# untitled.net
KiCad netlist of a schematic drawn in EAGLE
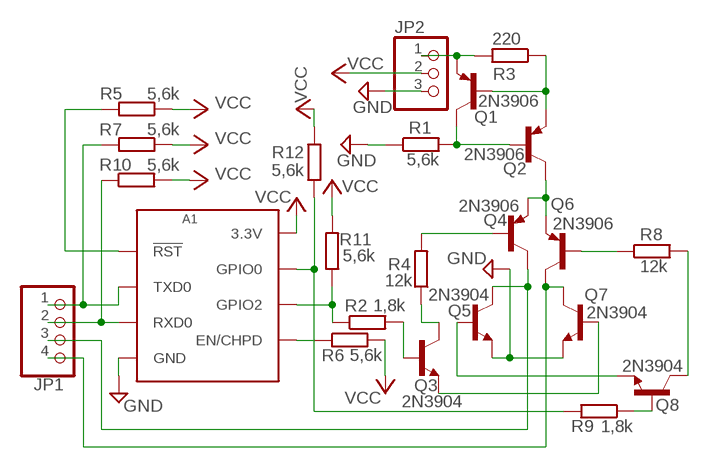
[diagram p0: schematic, sheet 1]

(export (version "E")
  (design (tool "Eeschema 10.0.6"))
  (components
    (comp (ref "A1")
      (value "ESP8266_ESP-01")
      (footprint "eagle-import:ESP8266_ESP-01_NO-SILKSCREEN")
      (libsource (lib "eagle-import") (part "ESP8266_ESP-?01"))
    )
    (comp (ref "JP1")
      (value "PINHD-1X4")
      (footprint "eagle-import:1X04")
      (libsource (lib "eagle-import") (part "PINHD-1X4"))
    )
    (comp (ref "JP2")
      (value "PINHD-1X3")
      (footprint "eagle-import:1X03")
      (libsource (lib "eagle-import") (part "PINHD-1X3"))
    )
    (comp (ref "Q1")
      (value "2N3906")
      (footprint "eagle-import:TO92-EBC")
      (libsource (lib "eagle-import") (part "-PNP-TO92-EBC2N3906"))
    )
    (comp (ref "Q2")
      (value "2N3906")
      (footprint "eagle-import:TO92-EBC")
      (libsource (lib "eagle-import") (part "-PNP-TO92-EBC2N3906"))
    )
    (comp (ref "Q3")
      (value "2N3904")
      (footprint "eagle-import:TO92-EBC")
      (libsource (lib "eagle-import") (part "-NPN-TO92-EBC2N3904"))
    )
    (comp (ref "Q4")
      (value "2N3906")
      (footprint "eagle-import:TO92-EBC")
      (libsource (lib "eagle-import") (part "-PNP-TO92-EBC2N3906"))
    )
    (comp (ref "Q5")
      (value "2N3904")
      (footprint "eagle-import:TO92-EBC")
      (libsource (lib "eagle-import") (part "-NPN-TO92-EBC2N3904"))
    )
    (comp (ref "Q6")
      (value "2N3906")
      (footprint "eagle-import:TO92-EBC")
      (libsource (lib "eagle-import") (part "-PNP-TO92-EBC2N3906"))
    )
    (comp (ref "Q7")
      (value "2N3904")
      (footprint "eagle-import:TO92-EBC")
      (libsource (lib "eagle-import") (part "-NPN-TO92-EBC2N3904"))
    )
    (comp (ref "Q8")
      (value "2N3904")
      (footprint "eagle-import:TO92-EBC")
      (libsource (lib "eagle-import") (part "-NPN-TO92-EBC2N3904"))
    )
    (comp (ref "R1")
      (value "5,6k")
      (footprint "eagle-import:0204_7")
      (libsource (lib "eagle-import") (part "R-EU_0204/7"))
    )
    (comp (ref "R2")
      (value "1,8k")
      (footprint "eagle-import:0204_7")
      (libsource (lib "eagle-import") (part "R-EU_0204/7"))
    )
    (comp (ref "R3")
      (value "220")
      (footprint "eagle-import:0204_7")
      (libsource (lib "eagle-import") (part "R-EU_0204/7"))
    )
    (comp (ref "R4")
      (value "12k")
      (footprint "eagle-import:0204_7")
      (libsource (lib "eagle-import") (part "R-EU_0204/7"))
    )
    (comp (ref "R5")
      (value "5,6k")
      (footprint "eagle-import:0204_7")
      (libsource (lib "eagle-import") (part "R-EU_0204/7"))
    )
    (comp (ref "R6")
      (value "5,6k")
      (footprint "eagle-import:0204_7")
      (libsource (lib "eagle-import") (part "R-EU_0204/7"))
    )
    (comp (ref "R7")
      (value "5,6k")
      (footprint "eagle-import:0204_7")
      (libsource (lib "eagle-import") (part "R-EU_0204/7"))
    )
    (comp (ref "R8")
      (value "12k")
      (footprint "eagle-import:0204_7")
      (libsource (lib "eagle-import") (part "R-EU_0204/7"))
    )
    (comp (ref "R9")
      (value "1,8k")
      (footprint "eagle-import:0204_7")
      (libsource (lib "eagle-import") (part "R-EU_0204/7"))
    )
    (comp (ref "R10")
      (value "5,6k")
      (footprint "eagle-import:0204_7")
      (libsource (lib "eagle-import") (part "R-EU_0204/7"))
    )
    (comp (ref "R11")
      (value "5,6k")
      (footprint "eagle-import:0204_7")
      (libsource (lib "eagle-import") (part "R-EU_0204/7"))
    )
    (comp (ref "R12")
      (value "5,6k")
      (footprint "eagle-import:0204_7")
      (libsource (lib "eagle-import") (part "R-EU_0204/7"))
    )
  )
  (nets
    (net (code "1") (name "GND") (class "Default")
      (node (ref "A1") (pin "GND") (pinfunction "GND_GND") (pintype "passive"))
      (node (ref "JP2") (pin "3") (pinfunction "3_3") (pintype "passive"))
      (node (ref "Q5") (pin "E") (pinfunction "E_E") (pintype "passive"))
      (node (ref "Q7") (pin "E") (pinfunction "E_E") (pintype "passive"))
      (node (ref "R1") (pin "1") (pinfunction "1_1") (pintype "passive"))
    )
    (net (code "2") (name "Net-(A1-EN{slash}CHPD)") (class "Default")
      (node (ref "A1") (pin "EN/CH_PD") (pinfunction "EN/CHPD_EN/CH_PD") (pintype "bidirectional"))
      (node (ref "R6") (pin "1") (pinfunction "1_1") (pintype "passive"))
    )
    (net (code "3") (name "Net-(A1-PadGPIO0)") (class "Default")
      (node (ref "A1") (pin "GPIO0") (pinfunction "GPIO0_GPIO0") (pintype "bidirectional"))
      (node (ref "R12") (pin "1") (pinfunction "1_1") (pintype "passive"))
      (node (ref "R9") (pin "2") (pinfunction "2_2") (pintype "passive"))
    )
    (net (code "4") (name "Net-(A1-PadGPIO2)") (class "Default")
      (node (ref "A1") (pin "GPIO2") (pinfunction "GPIO2_GPIO2") (pintype "bidirectional"))
      (node (ref "R11") (pin "1") (pinfunction "1_1") (pintype "passive"))
      (node (ref "R2") (pin "1") (pinfunction "1_1") (pintype "passive"))
    )
    (net (code "5") (name "Net-(A1-RXD0)") (class "Default")
      (node (ref "A1") (pin "RX") (pinfunction "RXD0_RX") (pintype "bidirectional"))
      (node (ref "JP1") (pin "2") (pinfunction "2_2") (pintype "passive"))
      (node (ref "R10") (pin "1") (pinfunction "1_1") (pintype "passive"))
    )
    (net (code "6") (name "Net-(A1-TXD0)") (class "Default")
      (node (ref "A1") (pin "TX") (pinfunction "TXD0_TX") (pintype "bidirectional"))
      (node (ref "JP1") (pin "1") (pinfunction "1_1") (pintype "passive"))
      (node (ref "R7") (pin "2") (pinfunction "2_2") (pintype "passive"))
    )
    (net (code "7") (name "Net-(A1-~{RST})") (class "Default")
      (node (ref "A1") (pin "RST") (pinfunction "~{RST}_RST") (pintype "bidirectional"))
      (node (ref "R5") (pin "2") (pinfunction "2_2") (pintype "passive"))
    )
    (net (code "8") (name "Net-(JP1-Pad3)") (class "Default")
      (node (ref "JP1") (pin "3") (pinfunction "3_3") (pintype "passive"))
      (node (ref "Q4") (pin "C") (pinfunction "C_C") (pintype "passive"))
      (node (ref "Q5") (pin "C") (pinfunction "C_C") (pintype "passive"))
    )
    (net (code "9") (name "Net-(JP1-Pad4)") (class "Default")
      (node (ref "JP1") (pin "4") (pinfunction "4_4") (pintype "passive"))
      (node (ref "Q6") (pin "C") (pinfunction "C_C") (pintype "passive"))
      (node (ref "Q7") (pin "C") (pinfunction "C_C") (pintype "passive"))
    )
    (net (code "10") (name "Net-(JP2-Pad1)") (class "Default")
      (node (ref "JP2") (pin "1") (pinfunction "1_1") (pintype "passive"))
      (node (ref "Q1") (pin "E") (pinfunction "E_E") (pintype "passive"))
      (node (ref "R3") (pin "2") (pinfunction "2_2") (pintype "passive"))
    )
    (net (code "11") (name "Net-(Q1-PadB)") (class "Default")
      (node (ref "Q1") (pin "B") (pinfunction "B_B") (pintype "passive"))
      (node (ref "Q2") (pin "E") (pinfunction "E_E") (pintype "passive"))
      (node (ref "R3") (pin "1") (pinfunction "1_1") (pintype "passive"))
    )
    (net (code "12") (name "Net-(Q1-PadC)") (class "Default")
      (node (ref "Q1") (pin "C") (pinfunction "C_C") (pintype "passive"))
      (node (ref "Q2") (pin "B") (pinfunction "B_B") (pintype "passive"))
      (node (ref "R1") (pin "2") (pinfunction "2_2") (pintype "passive"))
    )
    (net (code "13") (name "Net-(Q2-PadC)") (class "Default")
      (node (ref "Q2") (pin "C") (pinfunction "C_C") (pintype "passive"))
      (node (ref "Q4") (pin "E") (pinfunction "E_E") (pintype "passive"))
      (node (ref "Q6") (pin "E") (pinfunction "E_E") (pintype "passive"))
    )
    (net (code "14") (name "Net-(Q3-PadB)") (class "Default")
      (node (ref "Q3") (pin "B") (pinfunction "B_B") (pintype "passive"))
      (node (ref "R2") (pin "2") (pinfunction "2_2") (pintype "passive"))
    )
    (net (code "15") (name "Net-(Q3-PadC)") (class "Default")
      (node (ref "Q3") (pin "C") (pinfunction "C_C") (pintype "passive"))
      (node (ref "R4") (pin "1") (pinfunction "1_1") (pintype "passive"))
    )
    (net (code "16") (name "Net-(Q3-PadE)") (class "Default")
      (node (ref "Q3") (pin "E") (pinfunction "E_E") (pintype "passive"))
      (node (ref "Q7") (pin "B") (pinfunction "B_B") (pintype "passive"))
    )
    (net (code "17") (name "Net-(Q4-PadB)") (class "Default")
      (node (ref "Q4") (pin "B") (pinfunction "B_B") (pintype "passive"))
      (node (ref "R4") (pin "2") (pinfunction "2_2") (pintype "passive"))
    )
    (net (code "18") (name "Net-(Q5-PadB)") (class "Default")
      (node (ref "Q5") (pin "B") (pinfunction "B_B") (pintype "passive"))
      (node (ref "Q8") (pin "E") (pinfunction "E_E") (pintype "passive"))
    )
    (net (code "19") (name "Net-(Q6-PadB)") (class "Default")
      (node (ref "Q6") (pin "B") (pinfunction "B_B") (pintype "passive"))
      (node (ref "R8") (pin "1") (pinfunction "1_1") (pintype "passive"))
    )
    (net (code "20") (name "Net-(Q8-PadB)") (class "Default")
      (node (ref "Q8") (pin "B") (pinfunction "B_B") (pintype "passive"))
      (node (ref "R9") (pin "1") (pinfunction "1_1") (pintype "passive"))
    )
    (net (code "21") (name "Net-(Q8-PadC)") (class "Default")
      (node (ref "Q8") (pin "C") (pinfunction "C_C") (pintype "passive"))
      (node (ref "R8") (pin "2") (pinfunction "2_2") (pintype "passive"))
    )
    (net (code "22") (name "VCC") (class "Default")
      (node (ref "A1") (pin "3V3") (pinfunction "3.3V_3V3") (pintype "passive"))
      (node (ref "JP2") (pin "2") (pinfunction "2_2") (pintype "passive"))
      (node (ref "R10") (pin "2") (pinfunction "2_2") (pintype "passive"))
      (node (ref "R11") (pin "2") (pinfunction "2_2") (pintype "passive"))
      (node (ref "R12") (pin "2") (pinfunction "2_2") (pintype "passive"))
      (node (ref "R5") (pin "1") (pinfunction "1_1") (pintype "passive"))
      (node (ref "R6") (pin "2") (pinfunction "2_2") (pintype "passive"))
      (node (ref "R7") (pin "1") (pinfunction "1_1") (pintype "passive"))
    )
  )
)
